# PCB_Gabri1_1_1.net
KiCad netlist of a schematic drawn in EAGLE
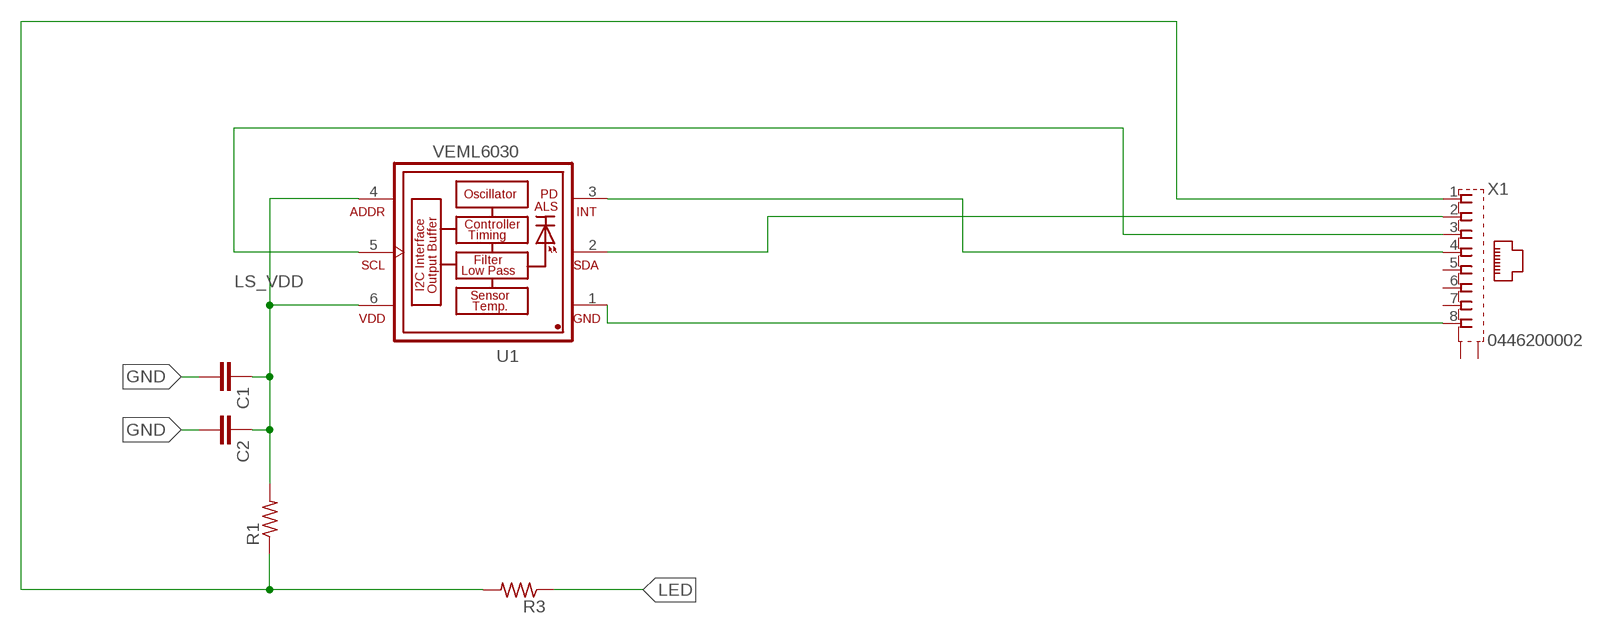
[diagram p0: schematic, sheet 1]

(export (version "E")
  (design (tool "Eeschema 10.0.6"))
  (components
    (comp (ref "C1")
      (value "C-EU025-024X044")
      (footprint "eagle-import:C025-024X044")
      (libsource (lib "eagle-import") (part "C-EU025-024X044"))
    )
    (comp (ref "C2")
      (value "C-EU025-024X044")
      (footprint "eagle-import:C025-024X044")
      (libsource (lib "eagle-import") (part "C-EU025-024X044"))
    )
    (comp (ref "R1")
      (value "R-US_R0805")
      (footprint "eagle-import:R0805")
      (libsource (lib "eagle-import") (part "R-US_R0805"))
    )
    (comp (ref "R3")
      (value "R-US_R0805")
      (footprint "eagle-import:R0805")
      (libsource (lib "eagle-import") (part "R-US_R0805"))
    )
    (comp (ref "U1")
      (value "VEML6030")
      (footprint "eagle-import:VISHAY_VEML6030_2X2X0.87")
      (fields (field (name "MF") "Vishay"))
      (libsource (lib "eagle-import") (part "VEML6030"))
    )
    (comp (ref "X1")
      (value "0446200002")
      (footprint "eagle-import:0446200002")
      (fields (field (name "MF") "Molex, LLC"))
      (libsource (lib "eagle-import") (part "0446200002"))
    )
  )
  (nets
    (net (code "1") (name "/LS_VDD") (class "Default")
      (node (ref "C1") (pin "1") (pinfunction "1_1") (pintype "passive"))
      (node (ref "C2") (pin "1") (pinfunction "1_1") (pintype "passive"))
      (node (ref "R1") (pin "2") (pinfunction "2_2") (pintype "passive"))
      (node (ref "U1") (pin "4") (pinfunction "ADDR_4") (pintype "bidirectional"))
      (node (ref "U1") (pin "6") (pinfunction "VDD_6") (pintype "power_in"))
    )
    (net (code "2") (name "GND") (class "Default")
      (node (ref "C1") (pin "2") (pinfunction "2_2") (pintype "passive"))
      (node (ref "C2") (pin "2") (pinfunction "2_2") (pintype "passive"))
      (node (ref "U1") (pin "1") (pinfunction "GND_1") (pintype "power_in"))
      (node (ref "X1") (pin "8") (pinfunction "8_8") (pintype "passive"))
    )
    (net (code "3") (name "LED") (class "Default")
      (node (ref "R3") (pin "1") (pinfunction "1_1") (pintype "passive"))
    )
    (net (code "4") (name "Net-(R1-Pad1)") (class "Default")
      (node (ref "R1") (pin "1") (pinfunction "1_1") (pintype "passive"))
      (node (ref "R3") (pin "2") (pinfunction "2_2") (pintype "passive"))
      (node (ref "X1") (pin "1") (pinfunction "1_1") (pintype "passive"))
    )
    (net (code "5") (name "Net-(U1-INT)") (class "Default")
      (node (ref "U1") (pin "3") (pinfunction "INT_3") (pintype "output"))
      (node (ref "X1") (pin "4") (pinfunction "4_4") (pintype "passive"))
    )
    (net (code "6") (name "Net-(U1-SCL)") (class "Default")
      (node (ref "U1") (pin "5") (pinfunction "SCL_5") (pintype "input"))
      (node (ref "X1") (pin "3") (pinfunction "3_3") (pintype "passive"))
    )
    (net (code "7") (name "Net-(U1-SDA)") (class "Default")
      (node (ref "U1") (pin "2") (pinfunction "SDA_2") (pintype "bidirectional"))
      (node (ref "X1") (pin "2") (pinfunction "2_2") (pintype "passive"))
    )
    (net (code "8") (name "unconnected-(X1-Pad5)") (class "Default")
      (node (ref "X1") (pin "5") (pinfunction "5_5") (pintype "passive"))
    )
    (net (code "9") (name "unconnected-(X1-Pad6)") (class "Default")
      (node (ref "X1") (pin "6") (pinfunction "6_6") (pintype "passive"))
    )
    (net (code "10") (name "unconnected-(X1-Pad7)") (class "Default")
      (node (ref "X1") (pin "7") (pinfunction "7_7") (pintype "passive"))
    )
    (net (code "11") (name "unconnected-(X1-S1-PadS@1)") (class "Default")
      (node (ref "X1") (pin "S@1") (pinfunction "S1_S@1") (pintype "passive"))
    )
    (net (code "12") (name "unconnected-(X1-S2-PadS@2)") (class "Default")
      (node (ref "X1") (pin "S@2") (pinfunction "S2_S@2") (pintype "passive"))
    )
  )
)
